# schematic_1_Fadlil.net
KiCad netlist of a schematic drawn in EAGLE
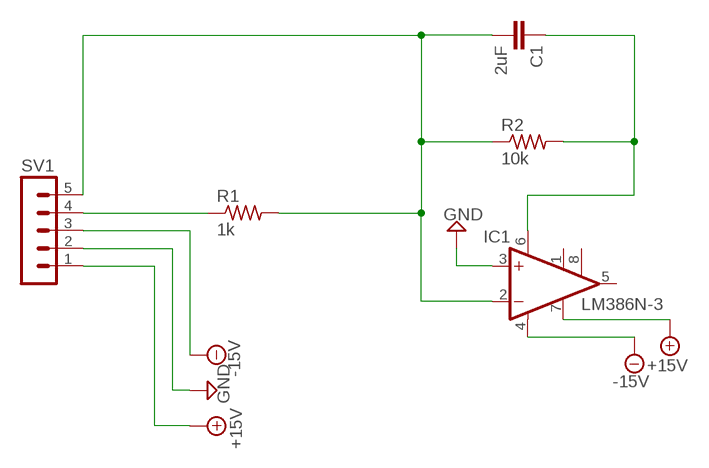
[diagram p0: schematic, sheet 1]

(export (version "E")
  (design (tool "Eeschema 10.0.6"))
  (components
    (comp (ref "C1")
      (value "2uF")
      (footprint "eagle-import:C2.5-3")
      (libsource (lib "eagle-import") (part "C2,5-3"))
    )
    (comp (ref "IC1")
      (value "LM386N-3")
      (footprint "eagle-import:DIL08")
      (libsource (lib "eagle-import") (part "LM386?-N3"))
    )
    (comp (ref "R1")
      (value "1k")
      (footprint "eagle-import:0204_7")
      (libsource (lib "eagle-import") (part "R-US_0204/7"))
    )
    (comp (ref "R2")
      (value "10k")
      (footprint "eagle-import:0204_7")
      (libsource (lib "eagle-import") (part "R-US_0204/7"))
    )
    (comp (ref "SV1")
      (value "MA05-1")
      (footprint "eagle-import:MA05-1")
      (libsource (lib "eagle-import") (part "MA05-1"))
    )
  )
  (nets
    (net (code "1") (name "+15V") (class "Default")
      (node (ref "IC1") (pin "7") (pinfunction "BYPASS_7") (pintype "passive"))
      (node (ref "SV1") (pin "1") (pinfunction "1_1") (pintype "passive"))
    )
    (net (code "2") (name "-15V") (class "Default")
      (node (ref "IC1") (pin "4") (pinfunction "GND_4") (pintype "power_in"))
      (node (ref "SV1") (pin "3") (pinfunction "3_3") (pintype "passive"))
    )
    (net (code "3") (name "GND") (class "Default")
      (node (ref "IC1") (pin "3") (pinfunction "+IN_3") (pintype "input"))
      (node (ref "SV1") (pin "2") (pinfunction "2_2") (pintype "passive"))
    )
    (net (code "4") (name "Net-(IC1--IN)") (class "Default")
      (node (ref "C1") (pin "2") (pinfunction "2_2") (pintype "passive"))
      (node (ref "IC1") (pin "2") (pinfunction "-IN_2") (pintype "input"))
      (node (ref "R1") (pin "2") (pinfunction "2_2") (pintype "passive"))
      (node (ref "R2") (pin "1") (pinfunction "1_1") (pintype "passive"))
      (node (ref "SV1") (pin "5") (pinfunction "5_5") (pintype "passive"))
    )
    (net (code "5") (name "Net-(IC1-VS)") (class "Default")
      (node (ref "C1") (pin "1") (pinfunction "1_1") (pintype "passive"))
      (node (ref "IC1") (pin "6") (pinfunction "VS_6") (pintype "power_in"))
      (node (ref "R2") (pin "2") (pinfunction "2_2") (pintype "passive"))
    )
    (net (code "6") (name "Net-(R1-Pad1)") (class "Default")
      (node (ref "R1") (pin "1") (pinfunction "1_1") (pintype "passive"))
      (node (ref "SV1") (pin "4") (pinfunction "4_4") (pintype "passive"))
    )
    (net (code "7") (name "unconnected-(IC1-GAIN-Pad1)") (class "Default")
      (node (ref "IC1") (pin "1") (pinfunction "GAIN_1") (pintype "passive"))
    )
    (net (code "8") (name "unconnected-(IC1-GAIN-Pad8)") (class "Default")
      (node (ref "IC1") (pin "8") (pinfunction "GAIN_8") (pintype "passive"))
    )
    (net (code "9") (name "unconnected-(IC1-OUT-Pad5)") (class "Default")
      (node (ref "IC1") (pin "5") (pinfunction "OUT_5") (pintype "output"))
    )
  )
)
